# Capsense.net
KiCad netlist of a schematic drawn in EAGLE
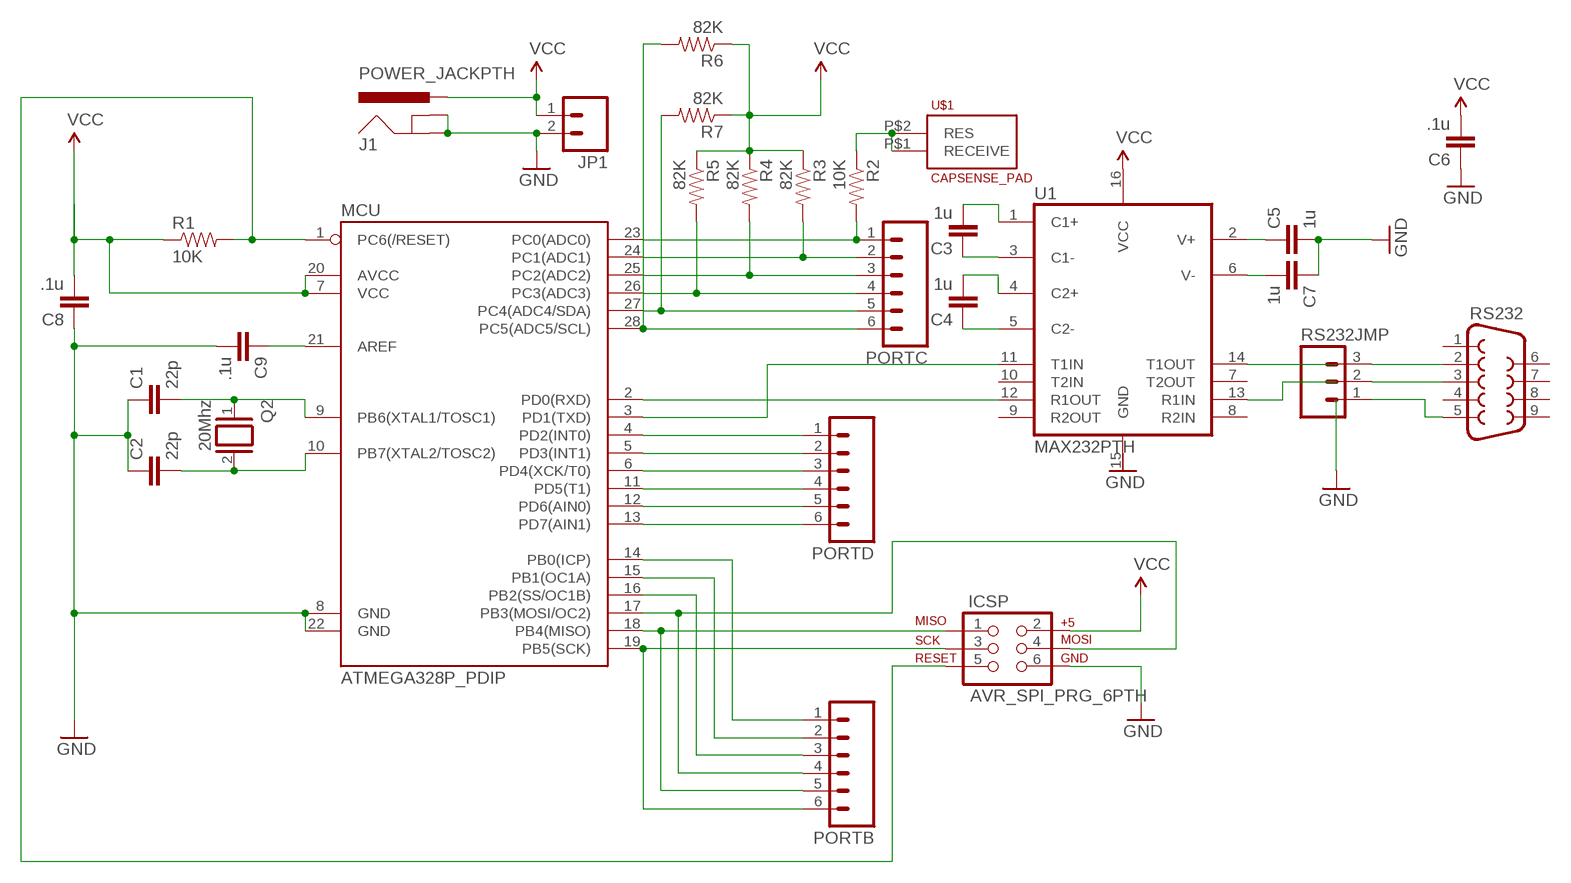
[diagram p0: schematic, sheet 1]

(export (version "E")
  (design (tool "Eeschema 10.0.6"))
  (components
    (comp (ref "C1")
      (value "22p")
      (footprint "eagle-import:AXIAL-5MM")
      (libsource (lib "eagle-import") (part "CAP_"))
    )
    (comp (ref "C2")
      (value "22p")
      (footprint "eagle-import:AXIAL-5MM")
      (libsource (lib "eagle-import") (part "CAP_"))
    )
    (comp (ref "C3")
      (value "1u")
      (footprint "eagle-import:AXIAL-5MM")
      (libsource (lib "eagle-import") (part "CAP_"))
    )
    (comp (ref "C4")
      (value "1u")
      (footprint "eagle-import:AXIAL-5MM")
      (libsource (lib "eagle-import") (part "CAP_"))
    )
    (comp (ref "C5")
      (value "1u")
      (footprint "eagle-import:AXIAL-5MM")
      (libsource (lib "eagle-import") (part "CAP_"))
    )
    (comp (ref "C6")
      (value ".1u")
      (footprint "eagle-import:AXIAL-5MM")
      (libsource (lib "eagle-import") (part "CAP_"))
    )
    (comp (ref "C7")
      (value "1u")
      (footprint "eagle-import:AXIAL-5MM")
      (libsource (lib "eagle-import") (part "CAP_"))
    )
    (comp (ref "C8")
      (value ".1u")
      (footprint "eagle-import:AXIAL-5MM")
      (libsource (lib "eagle-import") (part "CAP_"))
    )
    (comp (ref "C9")
      (value ".1u")
      (footprint "eagle-import:AXIAL-5MM")
      (libsource (lib "eagle-import") (part "CAP_"))
    )
    (comp (ref "ICSP")
      (value "AVR_SPI_PRG_6PTH")
      (footprint "eagle-import:2X3")
      (libsource (lib "eagle-import") (part "AVR_SPI_PRG_6PTH"))
    )
    (comp (ref "J1")
      (value "POWER_JACKPTH")
      (footprint "eagle-import:POWER_JACK_PTH")
      (libsource (lib "eagle-import") (part "POWER_JACKPTH"))
    )
    (comp (ref "JP1")
      (value "M02PTH")
      (footprint "eagle-import:1X02")
      (libsource (lib "eagle-import") (part "M02PTH"))
    )
    (comp (ref "MCU")
      (value "ATMEGA328P_PDIP")
      (footprint "eagle-import:DIL28-3")
      (libsource (lib "eagle-import") (part "ATMEGA328P_PDIP"))
    )
    (comp (ref "PORTB")
      (value "M06SIP")
      (footprint "eagle-import:1X06")
      (libsource (lib "eagle-import") (part "M06SIP"))
    )
    (comp (ref "PORTC")
      (value "M06SIP")
      (footprint "eagle-import:1X06")
      (libsource (lib "eagle-import") (part "M06SIP"))
    )
    (comp (ref "PORTD")
      (value "M06SIP")
      (footprint "eagle-import:1X06")
      (libsource (lib "eagle-import") (part "M06SIP"))
    )
    (comp (ref "Q2")
      (value "20Mhz")
      (footprint "eagle-import:QS")
      (libsource (lib "eagle-import") (part "XTAL/S"))
    )
    (comp (ref "R1")
      (value "10K")
      (footprint "eagle-import:AXIAL-0.3")
      (libsource (lib "eagle-import") (part "RESISTORAXIAL-0.3"))
    )
    (comp (ref "R2")
      (value "10K")
      (footprint "eagle-import:AXIAL-0.3")
      (libsource (lib "eagle-import") (part "RESISTORAXIAL-0.3"))
    )
    (comp (ref "R3")
      (value "82K")
      (footprint "eagle-import:AXIAL-0.3")
      (libsource (lib "eagle-import") (part "RESISTORAXIAL-0.3"))
    )
    (comp (ref "R4")
      (value "82K")
      (footprint "eagle-import:AXIAL-0.3")
      (libsource (lib "eagle-import") (part "RESISTORAXIAL-0.3"))
    )
    (comp (ref "R5")
      (value "82K")
      (footprint "eagle-import:AXIAL-0.3")
      (libsource (lib "eagle-import") (part "RESISTORAXIAL-0.3"))
    )
    (comp (ref "R6")
      (value "82K")
      (footprint "eagle-import:AXIAL-0.3")
      (libsource (lib "eagle-import") (part "RESISTORAXIAL-0.3"))
    )
    (comp (ref "R7")
      (value "82K")
      (footprint "eagle-import:AXIAL-0.3")
      (libsource (lib "eagle-import") (part "RESISTORAXIAL-0.3"))
    )
    (comp (ref "RS232")
      (value "DB9FEMALE")
      (footprint "eagle-import:DB9")
      (libsource (lib "eagle-import") (part "DB9FEMALE"))
    )
    (comp (ref "RS232JMP")
      (value "M03PTH")
      (footprint "eagle-import:1X03")
      (libsource (lib "eagle-import") (part "M03PTH"))
    )
    (comp (ref "U$1")
      (value "CAPSENSE_PAD")
      (footprint "eagle-import:CAPSENSE_PAD")
      (libsource (lib "eagle-import") (part "CAPSENSE_PAD"))
    )
    (comp (ref "U1")
      (value "MAX232PTH")
      (footprint "eagle-import:DIL16")
      (libsource (lib "eagle-import") (part "MAX232PTH"))
    )
  )
  (nets
    (net (code "1") (name "GND") (class "Default")
      (node (ref "C1") (pin "P$1") (pinfunction "1_P$1") (pintype "passive"))
      (node (ref "C2") (pin "P$1") (pinfunction "1_P$1") (pintype "passive"))
      (node (ref "C5") (pin "P$2") (pinfunction "2_P$2") (pintype "passive"))
      (node (ref "C6") (pin "P$1") (pinfunction "1_P$1") (pintype "passive"))
      (node (ref "C7") (pin "P$1") (pinfunction "1_P$1") (pintype "passive"))
      (node (ref "C8") (pin "P$1") (pinfunction "1_P$1") (pintype "passive"))
      (node (ref "C9") (pin "P$2") (pinfunction "2_P$2") (pintype "passive"))
      (node (ref "ICSP") (pin "6") (pinfunction "6_6") (pintype "passive"))
      (node (ref "J1") (pin "GND") (pinfunction "GND_GND") (pintype "bidirectional"))
      (node (ref "J1") (pin "GNDBREAK") (pinfunction "GNDBREAK_GNDBREAK") (pintype "bidirectional"))
      (node (ref "JP1") (pin "2") (pinfunction "2_2") (pintype "passive"))
      (node (ref "MCU") (pin "22") (pinfunction "GND_22") (pintype "bidirectional"))
      (node (ref "MCU") (pin "8") (pinfunction "GND_8") (pintype "bidirectional"))
    )
    (net (code "2") (name "Net-(C1-2)") (class "Default")
      (node (ref "C1") (pin "P$2") (pinfunction "2_P$2") (pintype "passive"))
      (node (ref "MCU") (pin "9") (pinfunction "PB6(XTAL1/TOSC1)_9") (pintype "bidirectional"))
      (node (ref "Q2") (pin "1") (pinfunction "1_1") (pintype "passive"))
    )
    (net (code "3") (name "Net-(C2-2)") (class "Default")
      (node (ref "C2") (pin "P$2") (pinfunction "2_P$2") (pintype "passive"))
      (node (ref "MCU") (pin "10") (pinfunction "PB7(XTAL2/TOSC2)_10") (pintype "bidirectional"))
      (node (ref "Q2") (pin "2") (pinfunction "2_2") (pintype "passive"))
    )
    (net (code "4") (name "Net-(C3-1)") (class "Default")
      (node (ref "C3") (pin "P$1") (pinfunction "1_P$1") (pintype "passive"))
      (node (ref "U1") (pin "3") (pinfunction "C1-_3") (pintype "bidirectional"))
    )
    (net (code "5") (name "Net-(C3-2)") (class "Default")
      (node (ref "C3") (pin "P$2") (pinfunction "2_P$2") (pintype "passive"))
      (node (ref "U1") (pin "1") (pinfunction "C1+_1") (pintype "bidirectional"))
    )
    (net (code "6") (name "Net-(C4-1)") (class "Default")
      (node (ref "C4") (pin "P$1") (pinfunction "1_P$1") (pintype "passive"))
      (node (ref "U1") (pin "5") (pinfunction "C2-_5") (pintype "bidirectional"))
    )
    (net (code "7") (name "Net-(C4-2)") (class "Default")
      (node (ref "C4") (pin "P$2") (pinfunction "2_P$2") (pintype "passive"))
      (node (ref "U1") (pin "4") (pinfunction "C2+_4") (pintype "bidirectional"))
    )
    (net (code "8") (name "Net-(C5-1)") (class "Default")
      (node (ref "C5") (pin "P$1") (pinfunction "1_P$1") (pintype "passive"))
      (node (ref "U1") (pin "2") (pinfunction "V+_2") (pintype "bidirectional"))
    )
    (net (code "9") (name "Net-(C7-2)") (class "Default")
      (node (ref "C7") (pin "P$2") (pinfunction "2_P$2") (pintype "passive"))
      (node (ref "U1") (pin "6") (pinfunction "V-_6") (pintype "bidirectional"))
    )
    (net (code "10") (name "Net-(C9-1)") (class "Default")
      (node (ref "C9") (pin "P$1") (pinfunction "1_P$1") (pintype "passive"))
      (node (ref "MCU") (pin "21") (pinfunction "AREF_21") (pintype "bidirectional"))
    )
    (net (code "11") (name "Net-(MCU-PB0(ICP))") (class "Default")
      (node (ref "MCU") (pin "14") (pinfunction "PB0(ICP)_14") (pintype "bidirectional"))
      (node (ref "PORTB") (pin "1") (pinfunction "1_1") (pintype "passive"))
    )
    (net (code "12") (name "Net-(MCU-PB1(OC1A))") (class "Default")
      (node (ref "MCU") (pin "15") (pinfunction "PB1(OC1A)_15") (pintype "bidirectional"))
      (node (ref "PORTB") (pin "2") (pinfunction "2_2") (pintype "passive"))
    )
    (net (code "13") (name "Net-(MCU-PB2(SS{slash}OC1B))") (class "Default")
      (node (ref "MCU") (pin "16") (pinfunction "PB2(SS/OC1B)_16") (pintype "bidirectional"))
      (node (ref "PORTB") (pin "3") (pinfunction "3_3") (pintype "passive"))
    )
    (net (code "14") (name "Net-(MCU-PB3(MOSI{slash}OC2))") (class "Default")
      (node (ref "ICSP") (pin "4") (pinfunction "4_4") (pintype "passive"))
      (node (ref "MCU") (pin "17") (pinfunction "PB3(MOSI/OC2)_17") (pintype "bidirectional"))
      (node (ref "PORTB") (pin "4") (pinfunction "4_4") (pintype "passive"))
    )
    (net (code "15") (name "Net-(MCU-PB4(MISO))") (class "Default")
      (node (ref "ICSP") (pin "1") (pinfunction "1_1") (pintype "passive"))
      (node (ref "MCU") (pin "18") (pinfunction "PB4(MISO)_18") (pintype "bidirectional"))
      (node (ref "PORTB") (pin "5") (pinfunction "5_5") (pintype "passive"))
    )
    (net (code "16") (name "Net-(MCU-PB5(SCK))") (class "Default")
      (node (ref "ICSP") (pin "3") (pinfunction "3_3") (pintype "passive"))
      (node (ref "MCU") (pin "19") (pinfunction "PB5(SCK)_19") (pintype "bidirectional"))
      (node (ref "PORTB") (pin "6") (pinfunction "6_6") (pintype "passive"))
    )
    (net (code "17") (name "Net-(MCU-PC0(ADC0))") (class "Default")
      (node (ref "MCU") (pin "23") (pinfunction "PC0(ADC0)_23") (pintype "bidirectional"))
      (node (ref "PORTC") (pin "1") (pinfunction "1_1") (pintype "passive"))
      (node (ref "R2") (pin "P$2") (pinfunction "2_P$2") (pintype "passive"))
    )
    (net (code "18") (name "Net-(MCU-PC1(ADC1))") (class "Default")
      (node (ref "MCU") (pin "24") (pinfunction "PC1(ADC1)_24") (pintype "bidirectional"))
      (node (ref "PORTC") (pin "2") (pinfunction "2_2") (pintype "passive"))
      (node (ref "R3") (pin "P$2") (pinfunction "2_P$2") (pintype "passive"))
    )
    (net (code "19") (name "Net-(MCU-PC2(ADC2))") (class "Default")
      (node (ref "MCU") (pin "25") (pinfunction "PC2(ADC2)_25") (pintype "bidirectional"))
      (node (ref "PORTC") (pin "3") (pinfunction "3_3") (pintype "passive"))
      (node (ref "R4") (pin "P$2") (pinfunction "2_P$2") (pintype "passive"))
    )
    (net (code "20") (name "Net-(MCU-PC3(ADC3))") (class "Default")
      (node (ref "MCU") (pin "26") (pinfunction "PC3(ADC3)_26") (pintype "bidirectional"))
      (node (ref "PORTC") (pin "4") (pinfunction "4_4") (pintype "passive"))
      (node (ref "R5") (pin "P$2") (pinfunction "2_P$2") (pintype "passive"))
    )
    (net (code "21") (name "Net-(MCU-PC4(ADC4{slash}SDA))") (class "Default")
      (node (ref "MCU") (pin "27") (pinfunction "PC4(ADC4/SDA)_27") (pintype "bidirectional"))
      (node (ref "PORTC") (pin "5") (pinfunction "5_5") (pintype "passive"))
      (node (ref "R7") (pin "P$2") (pinfunction "2_P$2") (pintype "passive"))
    )
    (net (code "22") (name "Net-(MCU-PC5(ADC5{slash}SCL))") (class "Default")
      (node (ref "MCU") (pin "28") (pinfunction "PC5(ADC5/SCL)_28") (pintype "bidirectional"))
      (node (ref "PORTC") (pin "6") (pinfunction "6_6") (pintype "passive"))
      (node (ref "R6") (pin "P$2") (pinfunction "2_P$2") (pintype "passive"))
    )
    (net (code "23") (name "Net-(MCU-PC6({slash}RESET))") (class "Default")
      (node (ref "ICSP") (pin "5") (pinfunction "5_5") (pintype "passive"))
      (node (ref "MCU") (pin "1") (pinfunction "PC6(/RESET)_1") (pintype "bidirectional"))
      (node (ref "R1") (pin "P$2") (pinfunction "2_P$2") (pintype "passive"))
    )
    (net (code "24") (name "Net-(MCU-PD0(RXD))") (class "Default")
      (node (ref "MCU") (pin "2") (pinfunction "PD0(RXD)_2") (pintype "bidirectional"))
      (node (ref "U1") (pin "12") (pinfunction "R1OUT_12") (pintype "output"))
    )
    (net (code "25") (name "Net-(MCU-PD1(TXD))") (class "Default")
      (node (ref "MCU") (pin "3") (pinfunction "PD1(TXD)_3") (pintype "bidirectional"))
      (node (ref "U1") (pin "11") (pinfunction "T1IN_11") (pintype "input"))
    )
    (net (code "26") (name "Net-(MCU-PD2(INT0))") (class "Default")
      (node (ref "MCU") (pin "4") (pinfunction "PD2(INT0)_4") (pintype "bidirectional"))
      (node (ref "PORTD") (pin "1") (pinfunction "1_1") (pintype "passive"))
    )
    (net (code "27") (name "Net-(MCU-PD3(INT1))") (class "Default")
      (node (ref "MCU") (pin "5") (pinfunction "PD3(INT1)_5") (pintype "bidirectional"))
      (node (ref "PORTD") (pin "2") (pinfunction "2_2") (pintype "passive"))
    )
    (net (code "28") (name "Net-(MCU-PD4(XCK{slash}T0))") (class "Default")
      (node (ref "MCU") (pin "6") (pinfunction "PD4(XCK/T0)_6") (pintype "bidirectional"))
      (node (ref "PORTD") (pin "3") (pinfunction "3_3") (pintype "passive"))
    )
    (net (code "29") (name "Net-(MCU-PD5(T1))") (class "Default")
      (node (ref "MCU") (pin "11") (pinfunction "PD5(T1)_11") (pintype "bidirectional"))
      (node (ref "PORTD") (pin "4") (pinfunction "4_4") (pintype "passive"))
    )
    (net (code "30") (name "Net-(MCU-PD6(AIN0))") (class "Default")
      (node (ref "MCU") (pin "12") (pinfunction "PD6(AIN0)_12") (pintype "bidirectional"))
      (node (ref "PORTD") (pin "5") (pinfunction "5_5") (pintype "passive"))
    )
    (net (code "31") (name "Net-(MCU-PD7(AIN1))") (class "Default")
      (node (ref "MCU") (pin "13") (pinfunction "PD7(AIN1)_13") (pintype "bidirectional"))
      (node (ref "PORTD") (pin "6") (pinfunction "6_6") (pintype "passive"))
    )
    (net (code "32") (name "Net-(R2-1)") (class "Default")
      (node (ref "R2") (pin "P$1") (pinfunction "1_P$1") (pintype "passive"))
      (node (ref "U$1") (pin "P$1") (pinfunction "RECEIVE_P$1") (pintype "bidirectional"))
      (node (ref "U$1") (pin "P$2") (pinfunction "RES_P$2") (pintype "bidirectional"))
    )
    (net (code "33") (name "Net-(RS232-Pad2)") (class "Default")
      (node (ref "RS232") (pin "2") (pinfunction "2_2") (pintype "passive"))
      (node (ref "RS232JMP") (pin "3") (pinfunction "3_3") (pintype "passive"))
    )
    (net (code "34") (name "Net-(RS232-Pad3)") (class "Default")
      (node (ref "RS232") (pin "3") (pinfunction "3_3") (pintype "passive"))
      (node (ref "RS232JMP") (pin "2") (pinfunction "2_2") (pintype "passive"))
    )
    (net (code "35") (name "Net-(RS232-Pad5)") (class "Default")
      (node (ref "RS232") (pin "5") (pinfunction "5_5") (pintype "passive"))
      (node (ref "RS232JMP") (pin "1") (pinfunction "1_1") (pintype "passive"))
    )
    (net (code "36") (name "VCC") (class "Default")
      (node (ref "C6") (pin "P$2") (pinfunction "2_P$2") (pintype "passive"))
      (node (ref "C8") (pin "P$2") (pinfunction "2_P$2") (pintype "passive"))
      (node (ref "ICSP") (pin "2") (pinfunction "2_2") (pintype "passive"))
      (node (ref "J1") (pin "PWR") (pinfunction "PWR_PWR") (pintype "bidirectional"))
      (node (ref "JP1") (pin "1") (pinfunction "1_1") (pintype "passive"))
      (node (ref "MCU") (pin "20") (pinfunction "AVCC_20") (pintype "bidirectional"))
      (node (ref "MCU") (pin "7") (pinfunction "VCC_7") (pintype "bidirectional"))
      (node (ref "R1") (pin "P$1") (pinfunction "1_P$1") (pintype "passive"))
      (node (ref "R3") (pin "P$1") (pinfunction "1_P$1") (pintype "passive"))
      (node (ref "R4") (pin "P$1") (pinfunction "1_P$1") (pintype "passive"))
      (node (ref "R5") (pin "P$1") (pinfunction "1_P$1") (pintype "passive"))
      (node (ref "R6") (pin "P$1") (pinfunction "1_P$1") (pintype "passive"))
      (node (ref "R7") (pin "P$1") (pinfunction "1_P$1") (pintype "passive"))
      (node (ref "U1") (pin "16") (pinfunction "VCC_16") (pintype "bidirectional"))
    )
    (net (code "37") (name "unconnected-(RS232-Pad1)") (class "Default")
      (node (ref "RS232") (pin "1") (pinfunction "1_1") (pintype "passive"))
    )
    (net (code "38") (name "unconnected-(RS232-Pad4)") (class "Default")
      (node (ref "RS232") (pin "4") (pinfunction "4_4") (pintype "passive"))
    )
    (net (code "39") (name "unconnected-(RS232-Pad6)") (class "Default")
      (node (ref "RS232") (pin "6") (pinfunction "6_6") (pintype "passive"))
    )
    (net (code "40") (name "unconnected-(RS232-Pad7)") (class "Default")
      (node (ref "RS232") (pin "7") (pinfunction "7_7") (pintype "passive"))
    )
    (net (code "41") (name "unconnected-(RS232-Pad8)") (class "Default")
      (node (ref "RS232") (pin "8") (pinfunction "8_8") (pintype "passive"))
    )
    (net (code "42") (name "unconnected-(RS232-Pad9)") (class "Default")
      (node (ref "RS232") (pin "9") (pinfunction "9_9") (pintype "passive"))
    )
    (net (code "43") (name "unconnected-(U1-GND-Pad15)") (class "Default")
      (node (ref "U1") (pin "15") (pinfunction "GND_15") (pintype "bidirectional"))
    )
    (net (code "44") (name "unconnected-(U1-R1IN-Pad13)") (class "Default")
      (node (ref "U1") (pin "13") (pinfunction "R1IN_13") (pintype "input"))
    )
    (net (code "45") (name "unconnected-(U1-R2IN-Pad8)") (class "Default")
      (node (ref "U1") (pin "8") (pinfunction "R2IN_8") (pintype "input"))
    )
    (net (code "46") (name "unconnected-(U1-R2OUT-Pad9)") (class "Default")
      (node (ref "U1") (pin "9") (pinfunction "R2OUT_9") (pintype "output"))
    )
    (net (code "47") (name "unconnected-(U1-T1OUT-Pad14)") (class "Default")
      (node (ref "U1") (pin "14") (pinfunction "T1OUT_14") (pintype "output"))
    )
    (net (code "48") (name "unconnected-(U1-T2IN-Pad10)") (class "Default")
      (node (ref "U1") (pin "10") (pinfunction "T2IN_10") (pintype "input"))
    )
    (net (code "49") (name "unconnected-(U1-T2OUT-Pad7)") (class "Default")
      (node (ref "U1") (pin "7") (pinfunction "T2OUT_7") (pintype "output"))
    )
  )
)
